# official.net
KiCad netlist of a schematic drawn in EAGLE
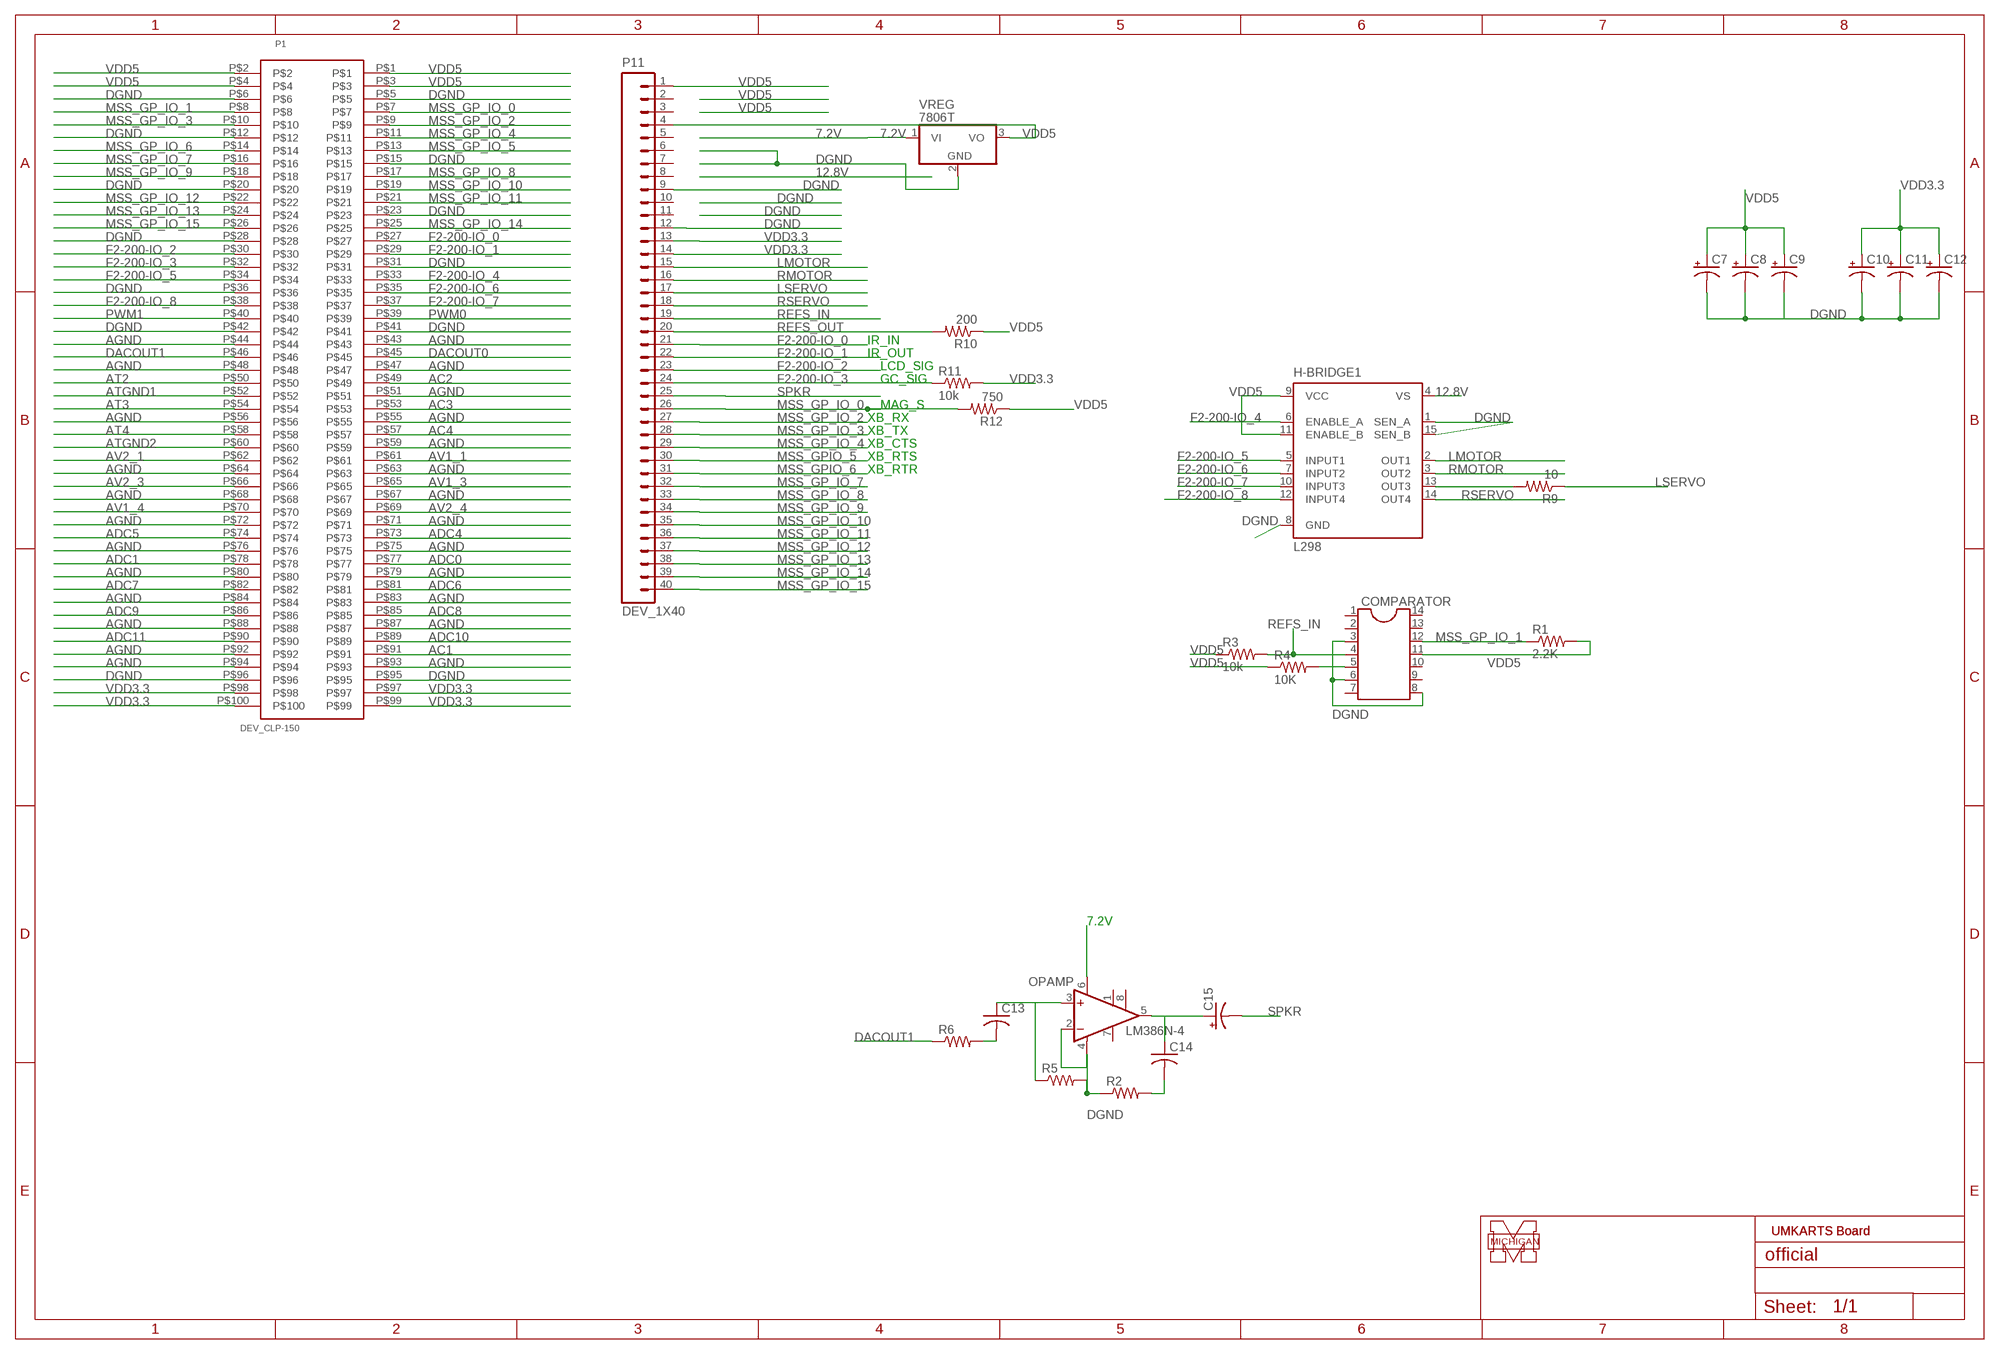
[diagram p0: schematic, sheet 1]

(export (version "E")
  (design (tool "Eeschema 10.0.6"))
  (components
    (comp (ref "C7")
      (value "CPOL-USB45181B")
      (footprint "eagle-import:B45181B")
      (libsource (lib "eagle-import") (part "CPOL-USB45181B"))
    )
    (comp (ref "C8")
      (value "CPOL-USB45181B")
      (footprint "eagle-import:B45181B")
      (libsource (lib "eagle-import") (part "CPOL-USB45181B"))
    )
    (comp (ref "C9")
      (value "CPOL-USB45181B")
      (footprint "eagle-import:B45181B")
      (libsource (lib "eagle-import") (part "CPOL-USB45181B"))
    )
    (comp (ref "C10")
      (value "CPOL-USB45181B")
      (footprint "eagle-import:B45181B")
      (libsource (lib "eagle-import") (part "CPOL-USB45181B"))
    )
    (comp (ref "C11")
      (value "CPOL-USB45181B")
      (footprint "eagle-import:B45181B")
      (libsource (lib "eagle-import") (part "CPOL-USB45181B"))
    )
    (comp (ref "C12")
      (value "CPOL-USB45181B")
      (footprint "eagle-import:B45181B")
      (libsource (lib "eagle-import") (part "CPOL-USB45181B"))
    )
    (comp (ref "C13")
      (value "C-US075-032X103")
      (footprint "eagle-import:C075-032X103")
      (libsource (lib "eagle-import") (part "C-US075-032X103"))
    )
    (comp (ref "C14")
      (value "C-US025-025X050")
      (footprint "eagle-import:C025-025X050")
      (libsource (lib "eagle-import") (part "C-US025-025X050"))
    )
    (comp (ref "C15")
      (value "CPOL-USB45181B")
      (footprint "eagle-import:B45181B")
      (libsource (lib "eagle-import") (part "CPOL-USB45181B"))
    )
    (comp (ref "COMPARATOR")
      (value "DIL14S")
      (footprint "eagle-import:SOCKET-14")
      (libsource (lib "eagle-import") (part "DIL14S"))
    )
    (comp (ref "H-BRIDGE1")
      (value "L298")
      (footprint "eagle-import:MULTIWATT-15")
      (fields (field (name "MPN") "L298N"))
      (libsource (lib "eagle-import") (part "L298"))
    )
    (comp (ref "OPAMP")
      (value "LM386N-4")
      (footprint "eagle-import:DIL08")
      (libsource (lib "eagle-import") (part "LM386?-N4"))
    )
    (comp (ref "P1")
      (value "DEV_CLP-150")
      (footprint "eagle-import:CLP-150")
      (libsource (lib "eagle-import") (part "DEV_CLP-150"))
    )
    (comp (ref "P11")
      (value "DEV_1X40")
      (footprint "eagle-import:1X40")
      (libsource (lib "eagle-import") (part "DEV_1X40"))
    )
    (comp (ref "R1")
      (value "2.2K")
      (footprint "eagle-import:0207_12")
      (libsource (lib "eagle-import") (part "R-US_0207/12"))
    )
    (comp (ref "R2")
      (value "R-US_0207/12")
      (footprint "eagle-import:0207_12")
      (libsource (lib "eagle-import") (part "R-US_0207/12"))
    )
    (comp (ref "R3")
      (value "10k")
      (footprint "eagle-import:0309_12")
      (libsource (lib "eagle-import") (part "R-US_0309/12"))
    )
    (comp (ref "R4")
      (value "10K")
      (footprint "eagle-import:0309_12")
      (libsource (lib "eagle-import") (part "R-US_0309/12"))
    )
    (comp (ref "R5")
      (value "R-US_0207/12")
      (footprint "eagle-import:0207_12")
      (libsource (lib "eagle-import") (part "R-US_0207/12"))
    )
    (comp (ref "R6")
      (value "R-US_0207/12")
      (footprint "eagle-import:0207_12")
      (libsource (lib "eagle-import") (part "R-US_0207/12"))
    )
    (comp (ref "R9")
      (value "10")
      (footprint "eagle-import:0309_12")
      (libsource (lib "eagle-import") (part "R-US_0309/12"))
    )
    (comp (ref "R10")
      (value "200")
      (footprint "eagle-import:0309_12")
      (libsource (lib "eagle-import") (part "R-US_0309/12"))
    )
    (comp (ref "R11")
      (value "10k")
      (footprint "eagle-import:0309_12")
      (libsource (lib "eagle-import") (part "R-US_0309/12"))
    )
    (comp (ref "R12")
      (value "750")
      (footprint "eagle-import:0309_12")
      (libsource (lib "eagle-import") (part "R-US_0309/12"))
    )
    (comp (ref "VREG")
      (value "7806T")
      (footprint "eagle-import:TO220H")
      (libsource (lib "eagle-import") (part "78T06"))
    )
  )
  (nets
    (net (code "1") (name "/7.2V") (class "Default")
      (node (ref "VREG") (pin "1") (pinfunction "VI_1") (pintype "input"))
    )
    (net (code "2") (name "/12.8V") (class "Default")
      (node (ref "H-BRIDGE1") (pin "4") (pinfunction "VS_4") (pintype "power_in"))
    )
    (net (code "3") (name "/AC1") (class "Default")
      (node (ref "P1") (pin "P$91") (pinfunction "P$91_P$91") (pintype "bidirectional"))
    )
    (net (code "4") (name "/AC2") (class "Default")
      (node (ref "P1") (pin "P$49") (pinfunction "P$49_P$49") (pintype "bidirectional"))
    )
    (net (code "5") (name "/AC3") (class "Default")
      (node (ref "P1") (pin "P$53") (pinfunction "P$53_P$53") (pintype "bidirectional"))
    )
    (net (code "6") (name "/AC4") (class "Default")
      (node (ref "P1") (pin "P$57") (pinfunction "P$57_P$57") (pintype "bidirectional"))
    )
    (net (code "7") (name "/ADC0") (class "Default")
      (node (ref "P1") (pin "P$77") (pinfunction "P$77_P$77") (pintype "bidirectional"))
    )
    (net (code "8") (name "/ADC1") (class "Default")
      (node (ref "P1") (pin "P$78") (pinfunction "P$78_P$78") (pintype "bidirectional"))
    )
    (net (code "9") (name "/ADC4") (class "Default")
      (node (ref "P1") (pin "P$73") (pinfunction "P$73_P$73") (pintype "bidirectional"))
    )
    (net (code "10") (name "/ADC5") (class "Default")
      (node (ref "P1") (pin "P$74") (pinfunction "P$74_P$74") (pintype "bidirectional"))
    )
    (net (code "11") (name "/ADC6") (class "Default")
      (node (ref "P1") (pin "P$81") (pinfunction "P$81_P$81") (pintype "bidirectional"))
    )
    (net (code "12") (name "/ADC7") (class "Default")
      (node (ref "P1") (pin "P$82") (pinfunction "P$82_P$82") (pintype "bidirectional"))
    )
    (net (code "13") (name "/ADC8") (class "Default")
      (node (ref "P1") (pin "P$85") (pinfunction "P$85_P$85") (pintype "bidirectional"))
    )
    (net (code "14") (name "/ADC9") (class "Default")
      (node (ref "P1") (pin "P$86") (pinfunction "P$86_P$86") (pintype "bidirectional"))
    )
    (net (code "15") (name "/ADC10") (class "Default")
      (node (ref "P1") (pin "P$89") (pinfunction "P$89_P$89") (pintype "bidirectional"))
    )
    (net (code "16") (name "/ADC11") (class "Default")
      (node (ref "P1") (pin "P$90") (pinfunction "P$90_P$90") (pintype "bidirectional"))
    )
    (net (code "17") (name "/AGND") (class "Default")
      (node (ref "P1") (pin "P$43") (pinfunction "P$43_P$43") (pintype "bidirectional"))
      (node (ref "P1") (pin "P$44") (pinfunction "P$44_P$44") (pintype "bidirectional"))
      (node (ref "P1") (pin "P$47") (pinfunction "P$47_P$47") (pintype "bidirectional"))
      (node (ref "P1") (pin "P$48") (pinfunction "P$48_P$48") (pintype "bidirectional"))
      (node (ref "P1") (pin "P$51") (pinfunction "P$51_P$51") (pintype "bidirectional"))
      (node (ref "P1") (pin "P$55") (pinfunction "P$55_P$55") (pintype "bidirectional"))
      (node (ref "P1") (pin "P$56") (pinfunction "P$56_P$56") (pintype "bidirectional"))
      (node (ref "P1") (pin "P$59") (pinfunction "P$59_P$59") (pintype "bidirectional"))
      (node (ref "P1") (pin "P$63") (pinfunction "P$63_P$63") (pintype "bidirectional"))
      (node (ref "P1") (pin "P$64") (pinfunction "P$64_P$64") (pintype "bidirectional"))
      (node (ref "P1") (pin "P$67") (pinfunction "P$67_P$67") (pintype "bidirectional"))
      (node (ref "P1") (pin "P$68") (pinfunction "P$68_P$68") (pintype "bidirectional"))
      (node (ref "P1") (pin "P$71") (pinfunction "P$71_P$71") (pintype "bidirectional"))
      (node (ref "P1") (pin "P$72") (pinfunction "P$72_P$72") (pintype "bidirectional"))
      (node (ref "P1") (pin "P$75") (pinfunction "P$75_P$75") (pintype "bidirectional"))
      (node (ref "P1") (pin "P$76") (pinfunction "P$76_P$76") (pintype "bidirectional"))
      (node (ref "P1") (pin "P$79") (pinfunction "P$79_P$79") (pintype "bidirectional"))
      (node (ref "P1") (pin "P$80") (pinfunction "P$80_P$80") (pintype "bidirectional"))
      (node (ref "P1") (pin "P$83") (pinfunction "P$83_P$83") (pintype "bidirectional"))
      (node (ref "P1") (pin "P$84") (pinfunction "P$84_P$84") (pintype "bidirectional"))
      (node (ref "P1") (pin "P$87") (pinfunction "P$87_P$87") (pintype "bidirectional"))
      (node (ref "P1") (pin "P$88") (pinfunction "P$88_P$88") (pintype "bidirectional"))
      (node (ref "P1") (pin "P$92") (pinfunction "P$92_P$92") (pintype "bidirectional"))
      (node (ref "P1") (pin "P$93") (pinfunction "P$93_P$93") (pintype "bidirectional"))
      (node (ref "P1") (pin "P$94") (pinfunction "P$94_P$94") (pintype "bidirectional"))
    )
    (net (code "18") (name "/AT2") (class "Default")
      (node (ref "P1") (pin "P$50") (pinfunction "P$50_P$50") (pintype "bidirectional"))
    )
    (net (code "19") (name "/AT3") (class "Default")
      (node (ref "P1") (pin "P$54") (pinfunction "P$54_P$54") (pintype "bidirectional"))
    )
    (net (code "20") (name "/AT4") (class "Default")
      (node (ref "P1") (pin "P$58") (pinfunction "P$58_P$58") (pintype "bidirectional"))
    )
    (net (code "21") (name "/ATGND1") (class "Default")
      (node (ref "P1") (pin "P$52") (pinfunction "P$52_P$52") (pintype "bidirectional"))
    )
    (net (code "22") (name "/ATGND2") (class "Default")
      (node (ref "P1") (pin "P$60") (pinfunction "P$60_P$60") (pintype "bidirectional"))
    )
    (net (code "23") (name "/AV1_1") (class "Default")
      (node (ref "P1") (pin "P$61") (pinfunction "P$61_P$61") (pintype "bidirectional"))
    )
    (net (code "24") (name "/AV1_3") (class "Default")
      (node (ref "P1") (pin "P$65") (pinfunction "P$65_P$65") (pintype "bidirectional"))
    )
    (net (code "25") (name "/AV1_4") (class "Default")
      (node (ref "P1") (pin "P$70") (pinfunction "P$70_P$70") (pintype "bidirectional"))
    )
    (net (code "26") (name "/AV2_1") (class "Default")
      (node (ref "P1") (pin "P$62") (pinfunction "P$62_P$62") (pintype "bidirectional"))
    )
    (net (code "27") (name "/AV2_3") (class "Default")
      (node (ref "P1") (pin "P$66") (pinfunction "P$66_P$66") (pintype "bidirectional"))
    )
    (net (code "28") (name "/AV2_4") (class "Default")
      (node (ref "P1") (pin "P$69") (pinfunction "P$69_P$69") (pintype "bidirectional"))
    )
    (net (code "29") (name "/DACOUT0") (class "Default")
      (node (ref "P1") (pin "P$45") (pinfunction "P$45_P$45") (pintype "bidirectional"))
    )
    (net (code "30") (name "/DACOUT1") (class "Default")
      (node (ref "P1") (pin "P$46") (pinfunction "P$46_P$46") (pintype "bidirectional"))
      (node (ref "R6") (pin "1") (pinfunction "1_1") (pintype "passive"))
    )
    (net (code "31") (name "/DGND") (class "Default")
      (node (ref "C10") (pin "-") (pinfunction "-_-") (pintype "passive"))
      (node (ref "C11") (pin "-") (pinfunction "-_-") (pintype "passive"))
      (node (ref "C12") (pin "-") (pinfunction "-_-") (pintype "passive"))
      (node (ref "C7") (pin "-") (pinfunction "-_-") (pintype "passive"))
      (node (ref "C8") (pin "-") (pinfunction "-_-") (pintype "passive"))
      (node (ref "C9") (pin "-") (pinfunction "-_-") (pintype "passive"))
      (node (ref "COMPARATOR") (pin "3") (pinfunction "3_3") (pintype "passive"))
      (node (ref "COMPARATOR") (pin "6") (pinfunction "6_6") (pintype "passive"))
      (node (ref "COMPARATOR") (pin "8") (pinfunction "8_8") (pintype "passive"))
      (node (ref "H-BRIDGE1") (pin "1") (pinfunction "SEN_A_1") (pintype "input"))
      (node (ref "H-BRIDGE1") (pin "15") (pinfunction "SEN_B_15") (pintype "input"))
      (node (ref "H-BRIDGE1") (pin "8") (pinfunction "GND_8") (pintype "power_in"))
      (node (ref "OPAMP") (pin "2") (pinfunction "-IN_2") (pintype "input"))
      (node (ref "OPAMP") (pin "4") (pinfunction "GND_4") (pintype "power_in"))
      (node (ref "P1") (pin "P$12") (pinfunction "P$12_P$12") (pintype "bidirectional"))
      (node (ref "P1") (pin "P$15") (pinfunction "P$15_P$15") (pintype "bidirectional"))
      (node (ref "P1") (pin "P$20") (pinfunction "P$20_P$20") (pintype "bidirectional"))
      (node (ref "P1") (pin "P$23") (pinfunction "P$23_P$23") (pintype "bidirectional"))
      (node (ref "P1") (pin "P$28") (pinfunction "P$28_P$28") (pintype "bidirectional"))
      (node (ref "P1") (pin "P$31") (pinfunction "P$31_P$31") (pintype "bidirectional"))
      (node (ref "P1") (pin "P$36") (pinfunction "P$36_P$36") (pintype "bidirectional"))
      (node (ref "P1") (pin "P$41") (pinfunction "P$41_P$41") (pintype "bidirectional"))
      (node (ref "P1") (pin "P$42") (pinfunction "P$42_P$42") (pintype "bidirectional"))
      (node (ref "P1") (pin "P$5") (pinfunction "P$5_P$5") (pintype "bidirectional"))
      (node (ref "P1") (pin "P$6") (pinfunction "P$6_P$6") (pintype "bidirectional"))
      (node (ref "P1") (pin "P$95") (pinfunction "P$95_P$95") (pintype "bidirectional"))
      (node (ref "P1") (pin "P$96") (pinfunction "P$96_P$96") (pintype "bidirectional"))
      (node (ref "P11") (pin "12") (pinfunction "12_12") (pintype "passive"))
      (node (ref "P11") (pin "9") (pinfunction "9_9") (pintype "passive"))
      (node (ref "R2") (pin "1") (pinfunction "1_1") (pintype "passive"))
      (node (ref "R5") (pin "2") (pinfunction "2_2") (pintype "passive"))
      (node (ref "VREG") (pin "2") (pinfunction "GND_2") (pintype "passive"))
    )
    (net (code "32") (name "/F2-200-IO_0") (class "Default")
      (node (ref "P1") (pin "P$27") (pinfunction "P$27_P$27") (pintype "bidirectional"))
      (node (ref "P11") (pin "21") (pinfunction "21_21") (pintype "passive"))
    )
    (net (code "33") (name "/F2-200-IO_1") (class "Default")
      (node (ref "P1") (pin "P$29") (pinfunction "P$29_P$29") (pintype "bidirectional"))
      (node (ref "P11") (pin "22") (pinfunction "22_22") (pintype "passive"))
    )
    (net (code "34") (name "/F2-200-IO_2") (class "Default")
      (node (ref "P1") (pin "P$30") (pinfunction "P$30_P$30") (pintype "bidirectional"))
      (node (ref "P11") (pin "23") (pinfunction "23_23") (pintype "passive"))
    )
    (net (code "35") (name "/F2-200-IO_3") (class "Default")
      (node (ref "P1") (pin "P$32") (pinfunction "P$32_P$32") (pintype "bidirectional"))
      (node (ref "P11") (pin "24") (pinfunction "24_24") (pintype "passive"))
      (node (ref "R11") (pin "1") (pinfunction "1_1") (pintype "passive"))
    )
    (net (code "36") (name "/F2-200-IO_4") (class "Default")
      (node (ref "H-BRIDGE1") (pin "6") (pinfunction "ENABLE_A_6") (pintype "input"))
      (node (ref "P1") (pin "P$33") (pinfunction "P$33_P$33") (pintype "bidirectional"))
    )
    (net (code "37") (name "/F2-200-IO_5") (class "Default")
      (node (ref "H-BRIDGE1") (pin "5") (pinfunction "INPUT1_5") (pintype "input"))
      (node (ref "P1") (pin "P$34") (pinfunction "P$34_P$34") (pintype "bidirectional"))
    )
    (net (code "38") (name "/F2-200-IO_6") (class "Default")
      (node (ref "H-BRIDGE1") (pin "7") (pinfunction "INPUT2_7") (pintype "input"))
      (node (ref "P1") (pin "P$35") (pinfunction "P$35_P$35") (pintype "bidirectional"))
    )
    (net (code "39") (name "/F2-200-IO_7") (class "Default")
      (node (ref "H-BRIDGE1") (pin "10") (pinfunction "INPUT3_10") (pintype "input"))
      (node (ref "P1") (pin "P$37") (pinfunction "P$37_P$37") (pintype "bidirectional"))
    )
    (net (code "40") (name "/F2-200-IO_8") (class "Default")
      (node (ref "H-BRIDGE1") (pin "12") (pinfunction "INPUT4_12") (pintype "input"))
      (node (ref "P1") (pin "P$38") (pinfunction "P$38_P$38") (pintype "bidirectional"))
    )
    (net (code "41") (name "/LMOTOR") (class "Default")
      (node (ref "H-BRIDGE1") (pin "2") (pinfunction "OUT1_2") (pintype "output"))
      (node (ref "P11") (pin "15") (pinfunction "15_15") (pintype "passive"))
    )
    (net (code "42") (name "/LSERVO") (class "Default")
      (node (ref "P11") (pin "17") (pinfunction "17_17") (pintype "passive"))
      (node (ref "R9") (pin "1") (pinfunction "1_1") (pintype "passive"))
    )
    (net (code "43") (name "/MSS_GPIO_5") (class "Default")
      (node (ref "P11") (pin "30") (pinfunction "30_30") (pintype "passive"))
    )
    (net (code "44") (name "/MSS_GPIO_6") (class "Default")
      (node (ref "P11") (pin "31") (pinfunction "31_31") (pintype "passive"))
    )
    (net (code "45") (name "/MSS_GP_IO_0") (class "Default")
      (node (ref "P1") (pin "P$7") (pinfunction "P$7_P$7") (pintype "bidirectional"))
      (node (ref "P11") (pin "26") (pinfunction "26_26") (pintype "passive"))
      (node (ref "R12") (pin "2") (pinfunction "2_2") (pintype "passive"))
    )
    (net (code "46") (name "/MSS_GP_IO_1") (class "Default")
      (node (ref "COMPARATOR") (pin "12") (pinfunction "12_12") (pintype "passive"))
      (node (ref "P1") (pin "P$8") (pinfunction "P$8_P$8") (pintype "bidirectional"))
      (node (ref "R1") (pin "1") (pinfunction "1_1") (pintype "passive"))
    )
    (net (code "47") (name "/MSS_GP_IO_2") (class "Default")
      (node (ref "P1") (pin "P$9") (pinfunction "P$9_P$9") (pintype "bidirectional"))
      (node (ref "P11") (pin "27") (pinfunction "27_27") (pintype "passive"))
    )
    (net (code "48") (name "/MSS_GP_IO_3") (class "Default")
      (node (ref "P1") (pin "P$10") (pinfunction "P$10_P$10") (pintype "bidirectional"))
      (node (ref "P11") (pin "28") (pinfunction "28_28") (pintype "passive"))
    )
    (net (code "49") (name "/MSS_GP_IO_4") (class "Default")
      (node (ref "P1") (pin "P$11") (pinfunction "P$11_P$11") (pintype "bidirectional"))
      (node (ref "P11") (pin "29") (pinfunction "29_29") (pintype "passive"))
    )
    (net (code "50") (name "/MSS_GP_IO_5") (class "Default")
      (node (ref "P1") (pin "P$13") (pinfunction "P$13_P$13") (pintype "bidirectional"))
    )
    (net (code "51") (name "/MSS_GP_IO_6") (class "Default")
      (node (ref "P1") (pin "P$14") (pinfunction "P$14_P$14") (pintype "bidirectional"))
    )
    (net (code "52") (name "/MSS_GP_IO_7") (class "Default")
      (node (ref "P1") (pin "P$16") (pinfunction "P$16_P$16") (pintype "bidirectional"))
      (node (ref "P11") (pin "32") (pinfunction "32_32") (pintype "passive"))
    )
    (net (code "53") (name "/MSS_GP_IO_8") (class "Default")
      (node (ref "P1") (pin "P$17") (pinfunction "P$17_P$17") (pintype "bidirectional"))
      (node (ref "P11") (pin "33") (pinfunction "33_33") (pintype "passive"))
    )
    (net (code "54") (name "/MSS_GP_IO_9") (class "Default")
      (node (ref "P1") (pin "P$18") (pinfunction "P$18_P$18") (pintype "bidirectional"))
      (node (ref "P11") (pin "34") (pinfunction "34_34") (pintype "passive"))
    )
    (net (code "55") (name "/MSS_GP_IO_10") (class "Default")
      (node (ref "P1") (pin "P$19") (pinfunction "P$19_P$19") (pintype "bidirectional"))
      (node (ref "P11") (pin "35") (pinfunction "35_35") (pintype "passive"))
    )
    (net (code "56") (name "/MSS_GP_IO_11") (class "Default")
      (node (ref "P1") (pin "P$21") (pinfunction "P$21_P$21") (pintype "bidirectional"))
      (node (ref "P11") (pin "36") (pinfunction "36_36") (pintype "passive"))
    )
    (net (code "57") (name "/MSS_GP_IO_12") (class "Default")
      (node (ref "P1") (pin "P$22") (pinfunction "P$22_P$22") (pintype "bidirectional"))
      (node (ref "P11") (pin "37") (pinfunction "37_37") (pintype "passive"))
    )
    (net (code "58") (name "/MSS_GP_IO_13") (class "Default")
      (node (ref "P1") (pin "P$24") (pinfunction "P$24_P$24") (pintype "bidirectional"))
      (node (ref "P11") (pin "38") (pinfunction "38_38") (pintype "passive"))
    )
    (net (code "59") (name "/MSS_GP_IO_14") (class "Default")
      (node (ref "P1") (pin "P$25") (pinfunction "P$25_P$25") (pintype "bidirectional"))
      (node (ref "P11") (pin "39") (pinfunction "39_39") (pintype "passive"))
    )
    (net (code "60") (name "/MSS_GP_IO_15") (class "Default")
      (node (ref "P1") (pin "P$26") (pinfunction "P$26_P$26") (pintype "bidirectional"))
      (node (ref "P11") (pin "40") (pinfunction "40_40") (pintype "passive"))
    )
    (net (code "61") (name "/PWM0") (class "Default")
      (node (ref "P1") (pin "P$39") (pinfunction "P$39_P$39") (pintype "bidirectional"))
    )
    (net (code "62") (name "/PWM1") (class "Default")
      (node (ref "P1") (pin "P$40") (pinfunction "P$40_P$40") (pintype "bidirectional"))
    )
    (net (code "63") (name "/REFS_IN") (class "Default")
      (node (ref "COMPARATOR") (pin "4") (pinfunction "4_4") (pintype "passive"))
      (node (ref "P11") (pin "19") (pinfunction "19_19") (pintype "passive"))
      (node (ref "R3") (pin "2") (pinfunction "2_2") (pintype "passive"))
    )
    (net (code "64") (name "/REFS_OUT") (class "Default")
      (node (ref "P11") (pin "20") (pinfunction "20_20") (pintype "passive"))
      (node (ref "R10") (pin "2") (pinfunction "2_2") (pintype "passive"))
    )
    (net (code "65") (name "/RMOTOR") (class "Default")
      (node (ref "H-BRIDGE1") (pin "3") (pinfunction "OUT2_3") (pintype "output"))
      (node (ref "P11") (pin "16") (pinfunction "16_16") (pintype "passive"))
    )
    (net (code "66") (name "/RSERVO") (class "Default")
      (node (ref "H-BRIDGE1") (pin "14") (pinfunction "OUT4_14") (pintype "output"))
      (node (ref "P11") (pin "18") (pinfunction "18_18") (pintype "passive"))
    )
    (net (code "67") (name "/SPKR") (class "Default")
      (node (ref "C15") (pin "-") (pinfunction "-_-") (pintype "passive"))
      (node (ref "P11") (pin "25") (pinfunction "25_25") (pintype "passive"))
    )
    (net (code "68") (name "/VDD3.3") (class "Default")
      (node (ref "C10") (pin "+") (pinfunction "+_+") (pintype "passive"))
      (node (ref "C11") (pin "+") (pinfunction "+_+") (pintype "passive"))
      (node (ref "C12") (pin "+") (pinfunction "+_+") (pintype "passive"))
      (node (ref "P1") (pin "P$100") (pinfunction "P$100_P$100") (pintype "bidirectional"))
      (node (ref "P1") (pin "P$97") (pinfunction "P$97_P$97") (pintype "bidirectional"))
      (node (ref "P1") (pin "P$98") (pinfunction "P$98_P$98") (pintype "bidirectional"))
      (node (ref "P1") (pin "P$99") (pinfunction "P$99_P$99") (pintype "bidirectional"))
      (node (ref "P11") (pin "13") (pinfunction "13_13") (pintype "passive"))
      (node (ref "P11") (pin "14") (pinfunction "14_14") (pintype "passive"))
      (node (ref "R11") (pin "2") (pinfunction "2_2") (pintype "passive"))
    )
    (net (code "69") (name "/VDD5") (class "Default")
      (node (ref "C7") (pin "+") (pinfunction "+_+") (pintype "passive"))
      (node (ref "C8") (pin "+") (pinfunction "+_+") (pintype "passive"))
      (node (ref "C9") (pin "+") (pinfunction "+_+") (pintype "passive"))
      (node (ref "COMPARATOR") (pin "11") (pinfunction "11_11") (pintype "passive"))
      (node (ref "H-BRIDGE1") (pin "11") (pinfunction "ENABLE_B_11") (pintype "input"))
      (node (ref "H-BRIDGE1") (pin "9") (pinfunction "VCC_9") (pintype "power_in"))
      (node (ref "P1") (pin "P$1") (pinfunction "P$1_P$1") (pintype "bidirectional"))
      (node (ref "P1") (pin "P$2") (pinfunction "P$2_P$2") (pintype "bidirectional"))
      (node (ref "P1") (pin "P$3") (pinfunction "P$3_P$3") (pintype "bidirectional"))
      (node (ref "P1") (pin "P$4") (pinfunction "P$4_P$4") (pintype "bidirectional"))
      (node (ref "P11") (pin "1") (pinfunction "1_1") (pintype "passive"))
      (node (ref "P11") (pin "4") (pinfunction "4_4") (pintype "passive"))
      (node (ref "R1") (pin "2") (pinfunction "2_2") (pintype "passive"))
      (node (ref "R10") (pin "1") (pinfunction "1_1") (pintype "passive"))
      (node (ref "R12") (pin "1") (pinfunction "1_1") (pintype "passive"))
      (node (ref "R3") (pin "1") (pinfunction "1_1") (pintype "passive"))
      (node (ref "R4") (pin "1") (pinfunction "1_1") (pintype "passive"))
      (node (ref "VREG") (pin "3") (pinfunction "VO_3") (pintype "passive"))
    )
    (net (code "70") (name "Net-(C13-Pad2)") (class "Default")
      (node (ref "C13") (pin "2") (pinfunction "2_2") (pintype "passive"))
      (node (ref "R6") (pin "2") (pinfunction "2_2") (pintype "passive"))
    )
    (net (code "71") (name "Net-(C14-Pad2)") (class "Default")
      (node (ref "C14") (pin "2") (pinfunction "2_2") (pintype "passive"))
      (node (ref "R2") (pin "2") (pinfunction "2_2") (pintype "passive"))
    )
    (net (code "72") (name "Net-(COMPARATOR-Pad5)") (class "Default")
      (node (ref "COMPARATOR") (pin "5") (pinfunction "5_5") (pintype "passive"))
      (node (ref "R4") (pin "2") (pinfunction "2_2") (pintype "passive"))
    )
    (net (code "73") (name "Net-(H-BRIDGE1-OUT3)") (class "Default")
      (node (ref "H-BRIDGE1") (pin "13") (pinfunction "OUT3_13") (pintype "output"))
      (node (ref "R9") (pin "2") (pinfunction "2_2") (pintype "passive"))
    )
    (net (code "74") (name "Net-(OPAMP-+IN)") (class "Default")
      (node (ref "C13") (pin "1") (pinfunction "1_1") (pintype "passive"))
      (node (ref "OPAMP") (pin "3") (pinfunction "+IN_3") (pintype "input"))
      (node (ref "R5") (pin "1") (pinfunction "1_1") (pintype "passive"))
    )
    (net (code "75") (name "Net-(OPAMP-OUT)") (class "Default")
      (node (ref "C14") (pin "1") (pinfunction "1_1") (pintype "passive"))
      (node (ref "C15") (pin "+") (pinfunction "+_+") (pintype "passive"))
      (node (ref "OPAMP") (pin "5") (pinfunction "OUT_5") (pintype "output"))
    )
    (net (code "76") (name "unconnected-(COMPARATOR-Pad1)") (class "Default")
      (node (ref "COMPARATOR") (pin "1") (pinfunction "1_1") (pintype "passive"))
    )
    (net (code "77") (name "unconnected-(COMPARATOR-Pad2)") (class "Default")
      (node (ref "COMPARATOR") (pin "2") (pinfunction "2_2") (pintype "passive"))
    )
    (net (code "78") (name "unconnected-(COMPARATOR-Pad7)") (class "Default")
      (node (ref "COMPARATOR") (pin "7") (pinfunction "7_7") (pintype "passive"))
    )
    (net (code "79") (name "unconnected-(COMPARATOR-Pad9)") (class "Default")
      (node (ref "COMPARATOR") (pin "9") (pinfunction "9_9") (pintype "passive"))
    )
    (net (code "80") (name "unconnected-(COMPARATOR-Pad10)") (class "Default")
      (node (ref "COMPARATOR") (pin "10") (pinfunction "10_10") (pintype "passive"))
    )
    (net (code "81") (name "unconnected-(COMPARATOR-Pad13)") (class "Default")
      (node (ref "COMPARATOR") (pin "13") (pinfunction "13_13") (pintype "passive"))
    )
    (net (code "82") (name "unconnected-(COMPARATOR-Pad14)") (class "Default")
      (node (ref "COMPARATOR") (pin "14") (pinfunction "14_14") (pintype "passive"))
    )
    (net (code "83") (name "unconnected-(OPAMP-BYPASS-Pad7)") (class "Default")
      (node (ref "OPAMP") (pin "7") (pinfunction "BYPASS_7") (pintype "passive"))
    )
    (net (code "84") (name "unconnected-(OPAMP-GAIN-Pad1)") (class "Default")
      (node (ref "OPAMP") (pin "1") (pinfunction "GAIN_1") (pintype "passive"))
    )
    (net (code "85") (name "unconnected-(OPAMP-GAIN-Pad8)") (class "Default")
      (node (ref "OPAMP") (pin "8") (pinfunction "GAIN_8") (pintype "passive"))
    )
    (net (code "86") (name "unconnected-(OPAMP-VS-Pad6)") (class "Default")
      (node (ref "OPAMP") (pin "6") (pinfunction "VS_6") (pintype "power_in"))
    )
    (net (code "87") (name "unconnected-(P11-Pad2)") (class "Default")
      (node (ref "P11") (pin "2") (pinfunction "2_2") (pintype "passive"))
    )
    (net (code "88") (name "unconnected-(P11-Pad3)") (class "Default")
      (node (ref "P11") (pin "3") (pinfunction "3_3") (pintype "passive"))
    )
    (net (code "89") (name "unconnected-(P11-Pad5)") (class "Default")
      (node (ref "P11") (pin "5") (pinfunction "5_5") (pintype "passive"))
    )
    (net (code "90") (name "unconnected-(P11-Pad6)") (class "Default")
      (node (ref "P11") (pin "6") (pinfunction "6_6") (pintype "passive"))
    )
    (net (code "91") (name "unconnected-(P11-Pad7)") (class "Default")
      (node (ref "P11") (pin "7") (pinfunction "7_7") (pintype "passive"))
    )
    (net (code "92") (name "unconnected-(P11-Pad8)") (class "Default")
      (node (ref "P11") (pin "8") (pinfunction "8_8") (pintype "passive"))
    )
    (net (code "93") (name "unconnected-(P11-Pad10)") (class "Default")
      (node (ref "P11") (pin "10") (pinfunction "10_10") (pintype "passive"))
    )
    (net (code "94") (name "unconnected-(P11-Pad11)") (class "Default")
      (node (ref "P11") (pin "11") (pinfunction "11_11") (pintype "passive"))
    )
  )
)
